# CAPT-A1-02_Cap_Touch_Slider_FeatherWing.net
KiCad netlist of a schematic drawn in EAGLE
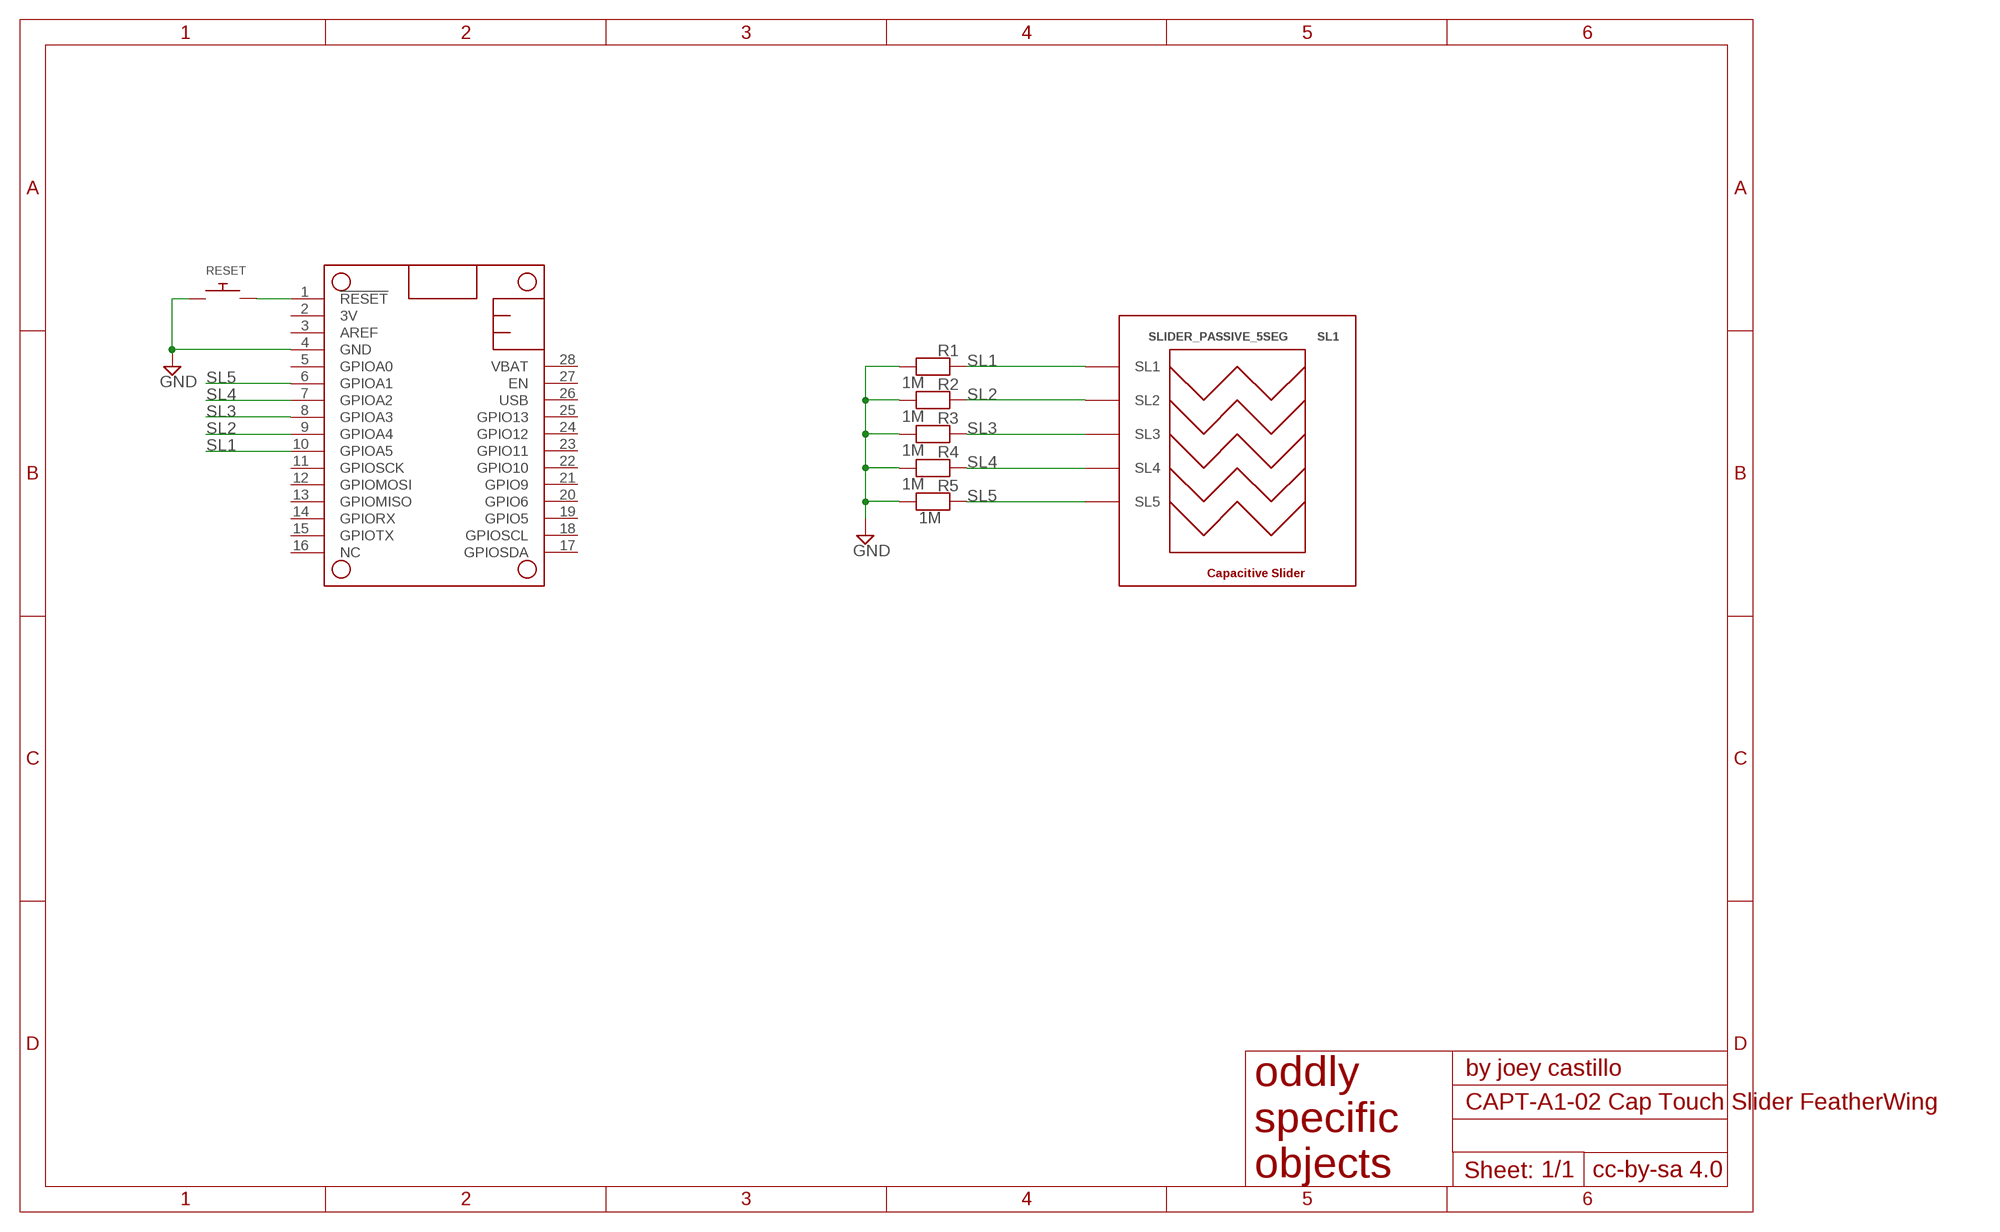
[diagram p0: schematic, sheet 1]

(export (version "E")
  (design (tool "Eeschema 10.0.6"))
  (components
    (comp (ref "MS1")
      (value "FEATHERWING")
      (footprint "eagle-import:FEATHERWING")
      (libsource (lib "eagle-import") (part "FEATHERWING"))
    )
    (comp (ref "R1")
      (value "1M")
      (footprint "eagle-import:0805-NO")
      (libsource (lib "eagle-import") (part "RESISTOR0805_NOOUTLINE"))
    )
    (comp (ref "R2")
      (value "1M")
      (footprint "eagle-import:0805-NO")
      (libsource (lib "eagle-import") (part "RESISTOR0805_NOOUTLINE"))
    )
    (comp (ref "R3")
      (value "1M")
      (footprint "eagle-import:0805-NO")
      (libsource (lib "eagle-import") (part "RESISTOR0805_NOOUTLINE"))
    )
    (comp (ref "R4")
      (value "1M")
      (footprint "eagle-import:0805-NO")
      (libsource (lib "eagle-import") (part "RESISTOR0805_NOOUTLINE"))
    )
    (comp (ref "R5")
      (value "1M")
      (footprint "eagle-import:0805-NO")
      (libsource (lib "eagle-import") (part "RESISTOR0805_NOOUTLINE"))
    )
    (comp (ref "RESET")
      (value "SPST_TACTILE_SWITCHRA-THRU")
      (footprint "eagle-import:MJTP1117")
      (libsource (lib "eagle-import") (part "SPST_TACTILE_SWITCHRA-THRU"))
    )
    (comp (ref "SL1")
      (value "SLIDER_PASSIVE_5SEG")
      (footprint "eagle-import:SLIDER_PASSIVE_5SEG_12MM")
      (libsource (lib "eagle-import") (part "SLIDER_PASSIVE_5SEG"))
    )
  )
  (nets
    (net (code "1") (name "/3V") (class "Default")
      (node (ref "MS1") (pin "2") (pinfunction "3V_2") (pintype "power_in"))
    )
    (net (code "2") (name "/SL1") (class "Default")
      (node (ref "MS1") (pin "10") (pinfunction "GPIOA5_10") (pintype "bidirectional"))
      (node (ref "R1") (pin "1") (pinfunction "1_1") (pintype "passive"))
      (node (ref "SL1") (pin "SL1") (pinfunction "SL1_SL1") (pintype "passive"))
    )
    (net (code "3") (name "/SL2") (class "Default")
      (node (ref "MS1") (pin "9") (pinfunction "GPIOA4_9") (pintype "bidirectional"))
      (node (ref "R2") (pin "1") (pinfunction "1_1") (pintype "passive"))
      (node (ref "SL1") (pin "SL2") (pinfunction "SL2_SL2") (pintype "passive"))
    )
    (net (code "4") (name "/SL3") (class "Default")
      (node (ref "MS1") (pin "8") (pinfunction "GPIOA3_8") (pintype "bidirectional"))
      (node (ref "R3") (pin "1") (pinfunction "1_1") (pintype "passive"))
      (node (ref "SL1") (pin "SL3") (pinfunction "SL3_SL3") (pintype "passive"))
    )
    (net (code "5") (name "/SL4") (class "Default")
      (node (ref "MS1") (pin "7") (pinfunction "GPIOA2_7") (pintype "bidirectional"))
      (node (ref "R4") (pin "1") (pinfunction "1_1") (pintype "passive"))
      (node (ref "SL1") (pin "SL4") (pinfunction "SL4_SL4") (pintype "passive"))
    )
    (net (code "6") (name "/SL5") (class "Default")
      (node (ref "MS1") (pin "6") (pinfunction "GPIOA1_6") (pintype "bidirectional"))
      (node (ref "R5") (pin "1") (pinfunction "1_1") (pintype "passive"))
      (node (ref "SL1") (pin "SL5") (pinfunction "SL5_SL5") (pintype "passive"))
    )
    (net (code "7") (name "/USB") (class "Default")
      (node (ref "MS1") (pin "26") (pinfunction "USB_26") (pintype "power_in"))
    )
    (net (code "8") (name "/VBAT") (class "Default")
      (node (ref "MS1") (pin "28") (pinfunction "VBAT_28") (pintype "power_in"))
    )
    (net (code "9") (name "GND") (class "Default")
      (node (ref "MS1") (pin "4") (pinfunction "GND_4") (pintype "power_in"))
      (node (ref "R1") (pin "2") (pinfunction "2_2") (pintype "passive"))
      (node (ref "R2") (pin "2") (pinfunction "2_2") (pintype "passive"))
      (node (ref "R3") (pin "2") (pinfunction "2_2") (pintype "passive"))
      (node (ref "R4") (pin "2") (pinfunction "2_2") (pintype "passive"))
      (node (ref "R5") (pin "2") (pinfunction "2_2") (pintype "passive"))
      (node (ref "RESET") (pin "P$1") (pinfunction "P$1_P$1") (pintype "passive"))
    )
    (net (code "10") (name "Net-(MS1-~{RESET})") (class "Default")
      (node (ref "MS1") (pin "1") (pinfunction "~{RESET}_1") (pintype "input"))
      (node (ref "RESET") (pin "P$2") (pinfunction "P$2_P$2") (pintype "passive"))
    )
    (net (code "11") (name "unconnected-(MS1-AREF-Pad3)") (class "Default")
      (node (ref "MS1") (pin "3") (pinfunction "AREF_3") (pintype "passive"))
    )
    (net (code "12") (name "unconnected-(MS1-EN-Pad27)") (class "Default")
      (node (ref "MS1") (pin "27") (pinfunction "EN_27") (pintype "passive"))
    )
    (net (code "13") (name "unconnected-(MS1-GPIO5-Pad19)") (class "Default")
      (node (ref "MS1") (pin "19") (pinfunction "GPIO5_19") (pintype "bidirectional"))
    )
    (net (code "14") (name "unconnected-(MS1-GPIO6-Pad20)") (class "Default")
      (node (ref "MS1") (pin "20") (pinfunction "GPIO6_20") (pintype "bidirectional"))
    )
    (net (code "15") (name "unconnected-(MS1-GPIO9-Pad21)") (class "Default")
      (node (ref "MS1") (pin "21") (pinfunction "GPIO9_21") (pintype "bidirectional"))
    )
    (net (code "16") (name "unconnected-(MS1-GPIO10-Pad22)") (class "Default")
      (node (ref "MS1") (pin "22") (pinfunction "GPIO10_22") (pintype "bidirectional"))
    )
    (net (code "17") (name "unconnected-(MS1-GPIO11-Pad23)") (class "Default")
      (node (ref "MS1") (pin "23") (pinfunction "GPIO11_23") (pintype "bidirectional"))
    )
    (net (code "18") (name "unconnected-(MS1-GPIO12-Pad24)") (class "Default")
      (node (ref "MS1") (pin "24") (pinfunction "GPIO12_24") (pintype "bidirectional"))
    )
    (net (code "19") (name "unconnected-(MS1-GPIO13-Pad25)") (class "Default")
      (node (ref "MS1") (pin "25") (pinfunction "GPIO13_25") (pintype "bidirectional"))
    )
    (net (code "20") (name "unconnected-(MS1-GPIOA0-Pad5)") (class "Default")
      (node (ref "MS1") (pin "5") (pinfunction "GPIOA0_5") (pintype "bidirectional"))
    )
    (net (code "21") (name "unconnected-(MS1-GPIOMISO-Pad13)") (class "Default")
      (node (ref "MS1") (pin "13") (pinfunction "GPIOMISO_13") (pintype "bidirectional"))
    )
    (net (code "22") (name "unconnected-(MS1-GPIOMOSI-Pad12)") (class "Default")
      (node (ref "MS1") (pin "12") (pinfunction "GPIOMOSI_12") (pintype "bidirectional"))
    )
    (net (code "23") (name "unconnected-(MS1-GPIORX-Pad14)") (class "Default")
      (node (ref "MS1") (pin "14") (pinfunction "GPIORX_14") (pintype "bidirectional"))
    )
    (net (code "24") (name "unconnected-(MS1-GPIOSCK-Pad11)") (class "Default")
      (node (ref "MS1") (pin "11") (pinfunction "GPIOSCK_11") (pintype "bidirectional"))
    )
    (net (code "25") (name "unconnected-(MS1-GPIOSCL-Pad18)") (class "Default")
      (node (ref "MS1") (pin "18") (pinfunction "GPIOSCL_18") (pintype "bidirectional"))
    )
    (net (code "26") (name "unconnected-(MS1-GPIOSDA-Pad17)") (class "Default")
      (node (ref "MS1") (pin "17") (pinfunction "GPIOSDA_17") (pintype "bidirectional"))
    )
    (net (code "27") (name "unconnected-(MS1-GPIOTX-Pad15)") (class "Default")
      (node (ref "MS1") (pin "15") (pinfunction "GPIOTX_15") (pintype "bidirectional"))
    )
    (net (code "28") (name "unconnected-(MS1-NC-Pad16)") (class "Default")
      (node (ref "MS1") (pin "16") (pinfunction "NC_16") (pintype "passive"))
    )
  )
)
